# sine_wave_generator.net
KiCad netlist of a schematic drawn in Altium Designer
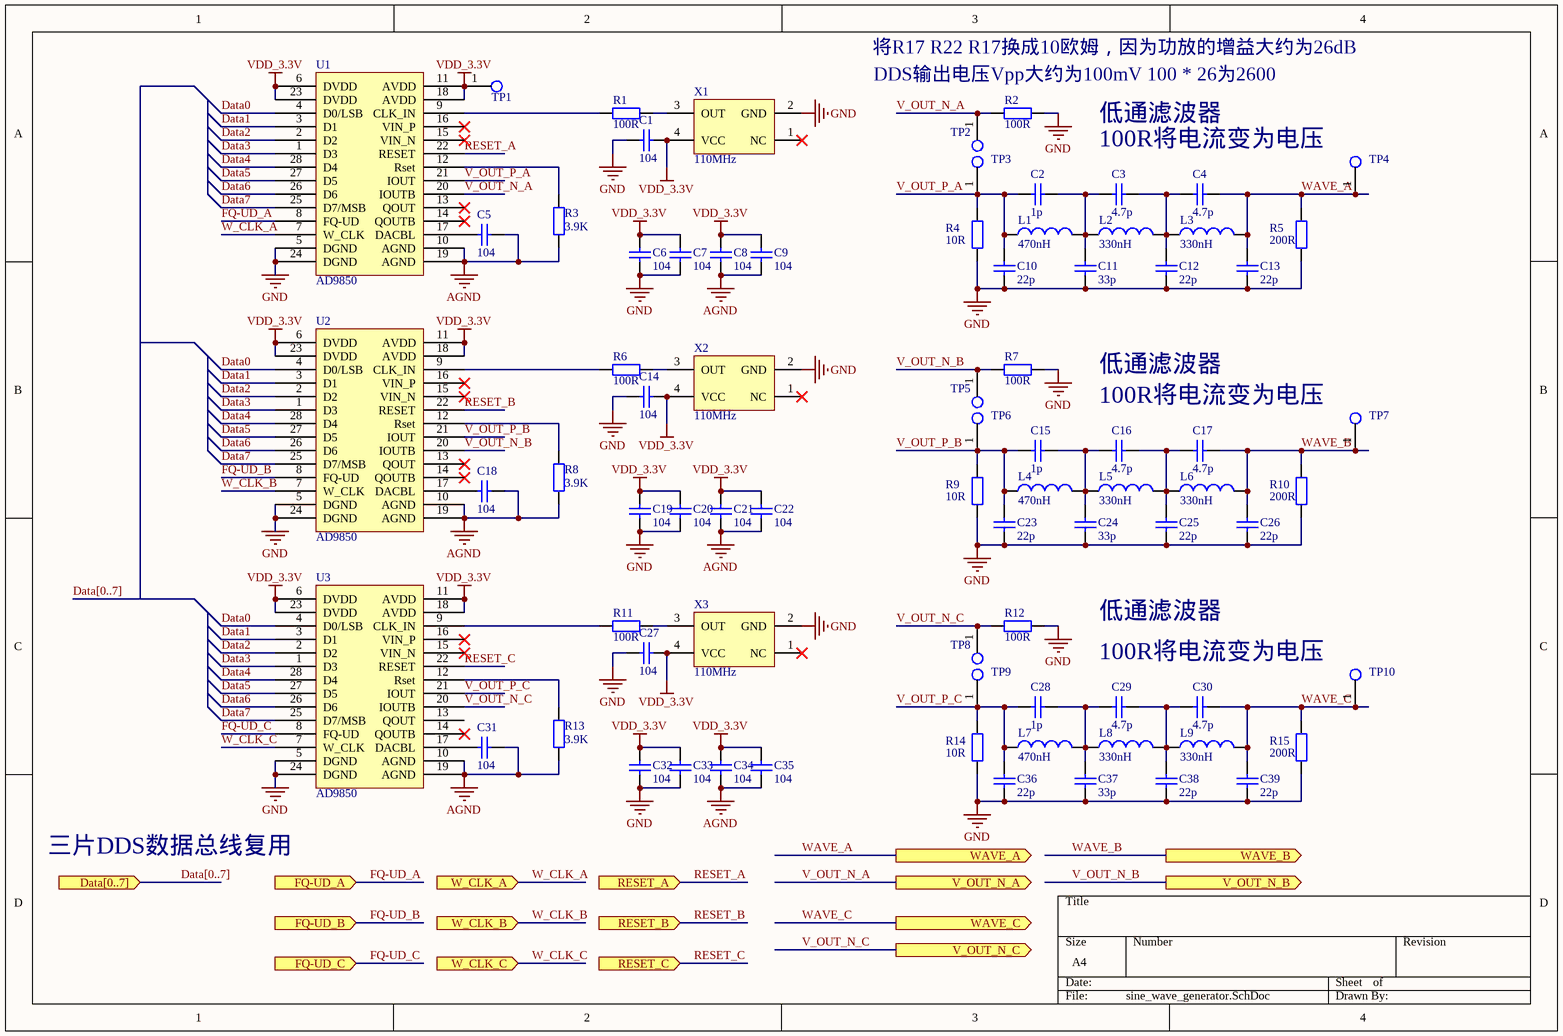
[diagram p0: sine_wave_generator.SchDoc]

(export (version "E")
  (design (tool "Eeschema 10.0.6"))
  (components
    (comp (ref "C1")
      (value "104")
      (footprint "0805")
      (fields (field (name "Comment") "Cap"))
      (libsource (lib "自动化研究所集成库20170318") (part "Cap"))
    )
    (comp (ref "C2")
      (value "1p")
      (footprint "0805")
      (fields (field (name "Comment") "Cap"))
      (libsource (lib "自动化研究所集成库20170318") (part "Cap"))
    )
    (comp (ref "C3")
      (value "4.7p")
      (footprint "0805")
      (fields (field (name "Comment") "Cap"))
      (libsource (lib "自动化研究所集成库20170318") (part "Cap"))
    )
    (comp (ref "C4")
      (value "4.7p")
      (footprint "0805")
      (fields (field (name "Comment") "Cap"))
      (libsource (lib "自动化研究所集成库20170318") (part "Cap"))
    )
    (comp (ref "C5")
      (value "104")
      (footprint "0805")
      (fields (field (name "Comment") "Cap"))
      (libsource (lib "自动化研究所集成库20170318") (part "Cap"))
    )
    (comp (ref "C6")
      (value "104")
      (footprint "0805")
      (fields (field (name "Comment") "Cap"))
      (libsource (lib "自动化研究所集成库20170318") (part "Cap"))
    )
    (comp (ref "C7")
      (value "104")
      (footprint "0805")
      (fields (field (name "Comment") "Cap"))
      (libsource (lib "自动化研究所集成库20170318") (part "Cap"))
    )
    (comp (ref "C8")
      (value "104")
      (footprint "0805")
      (fields (field (name "Comment") "Cap"))
      (libsource (lib "自动化研究所集成库20170318") (part "Cap"))
    )
    (comp (ref "C9")
      (value "104")
      (footprint "0805")
      (fields (field (name "Comment") "Cap"))
      (libsource (lib "自动化研究所集成库20170318") (part "Cap"))
    )
    (comp (ref "C10")
      (value "22p")
      (footprint "0805")
      (fields (field (name "Comment") "Cap"))
      (libsource (lib "自动化研究所集成库20170318") (part "Cap"))
    )
    (comp (ref "C11")
      (value "33p")
      (footprint "0805")
      (fields (field (name "Comment") "Cap"))
      (libsource (lib "自动化研究所集成库20170318") (part "Cap"))
    )
    (comp (ref "C12")
      (value "22p")
      (footprint "0805")
      (fields (field (name "Comment") "Cap"))
      (libsource (lib "自动化研究所集成库20170318") (part "Cap"))
    )
    (comp (ref "C13")
      (value "22p")
      (footprint "0805")
      (fields (field (name "Comment") "Cap"))
      (libsource (lib "自动化研究所集成库20170318") (part "Cap"))
    )
    (comp (ref "C14")
      (value "104")
      (footprint "0805")
      (fields (field (name "Comment") "Cap"))
      (libsource (lib "自动化研究所集成库20170318") (part "Cap"))
    )
    (comp (ref "C15")
      (value "1p")
      (footprint "0805")
      (fields (field (name "Comment") "Cap"))
      (libsource (lib "自动化研究所集成库20170318") (part "Cap"))
    )
    (comp (ref "C16")
      (value "4.7p")
      (footprint "0805")
      (fields (field (name "Comment") "Cap"))
      (libsource (lib "自动化研究所集成库20170318") (part "Cap"))
    )
    (comp (ref "C17")
      (value "4.7p")
      (footprint "0805")
      (fields (field (name "Comment") "Cap"))
      (libsource (lib "自动化研究所集成库20170318") (part "Cap"))
    )
    (comp (ref "C18")
      (value "104")
      (footprint "0805")
      (fields (field (name "Comment") "Cap"))
      (libsource (lib "自动化研究所集成库20170318") (part "Cap"))
    )
    (comp (ref "C19")
      (value "104")
      (footprint "0805")
      (fields (field (name "Comment") "Cap"))
      (libsource (lib "自动化研究所集成库20170318") (part "Cap"))
    )
    (comp (ref "C20")
      (value "104")
      (footprint "0805")
      (fields (field (name "Comment") "Cap"))
      (libsource (lib "自动化研究所集成库20170318") (part "Cap"))
    )
    (comp (ref "C21")
      (value "104")
      (footprint "0805")
      (fields (field (name "Comment") "Cap"))
      (libsource (lib "自动化研究所集成库20170318") (part "Cap"))
    )
    (comp (ref "C22")
      (value "104")
      (footprint "0805")
      (fields (field (name "Comment") "Cap"))
      (libsource (lib "自动化研究所集成库20170318") (part "Cap"))
    )
    (comp (ref "C23")
      (value "22p")
      (footprint "0805")
      (fields (field (name "Comment") "Cap"))
      (libsource (lib "自动化研究所集成库20170318") (part "Cap"))
    )
    (comp (ref "C24")
      (value "33p")
      (footprint "0805")
      (fields (field (name "Comment") "Cap"))
      (libsource (lib "自动化研究所集成库20170318") (part "Cap"))
    )
    (comp (ref "C25")
      (value "22p")
      (footprint "0805")
      (fields (field (name "Comment") "Cap"))
      (libsource (lib "自动化研究所集成库20170318") (part "Cap"))
    )
    (comp (ref "C26")
      (value "22p")
      (footprint "0805")
      (fields (field (name "Comment") "Cap"))
      (libsource (lib "自动化研究所集成库20170318") (part "Cap"))
    )
    (comp (ref "C27")
      (value "104")
      (footprint "0805")
      (fields (field (name "Comment") "Cap"))
      (libsource (lib "自动化研究所集成库20170318") (part "Cap"))
    )
    (comp (ref "C28")
      (value "1p")
      (footprint "0805")
      (fields (field (name "Comment") "Cap"))
      (libsource (lib "自动化研究所集成库20170318") (part "Cap"))
    )
    (comp (ref "C29")
      (value "4.7p")
      (footprint "0805")
      (fields (field (name "Comment") "Cap"))
      (libsource (lib "自动化研究所集成库20170318") (part "Cap"))
    )
    (comp (ref "C30")
      (value "4.7p")
      (footprint "0805")
      (fields (field (name "Comment") "Cap"))
      (libsource (lib "自动化研究所集成库20170318") (part "Cap"))
    )
    (comp (ref "C31")
      (value "104")
      (footprint "0805")
      (fields (field (name "Comment") "Cap"))
      (libsource (lib "自动化研究所集成库20170318") (part "Cap"))
    )
    (comp (ref "C32")
      (value "104")
      (footprint "0805")
      (fields (field (name "Comment") "Cap"))
      (libsource (lib "自动化研究所集成库20170318") (part "Cap"))
    )
    (comp (ref "C33")
      (value "104")
      (footprint "0805")
      (fields (field (name "Comment") "Cap"))
      (libsource (lib "自动化研究所集成库20170318") (part "Cap"))
    )
    (comp (ref "C34")
      (value "104")
      (footprint "0805")
      (fields (field (name "Comment") "Cap"))
      (libsource (lib "自动化研究所集成库20170318") (part "Cap"))
    )
    (comp (ref "C35")
      (value "104")
      (footprint "0805")
      (fields (field (name "Comment") "Cap"))
      (libsource (lib "自动化研究所集成库20170318") (part "Cap"))
    )
    (comp (ref "C36")
      (value "22p")
      (footprint "0805")
      (fields (field (name "Comment") "Cap"))
      (libsource (lib "自动化研究所集成库20170318") (part "Cap"))
    )
    (comp (ref "C37")
      (value "33p")
      (footprint "0805")
      (fields (field (name "Comment") "Cap"))
      (libsource (lib "自动化研究所集成库20170318") (part "Cap"))
    )
    (comp (ref "C38")
      (value "22p")
      (footprint "0805")
      (fields (field (name "Comment") "Cap"))
      (libsource (lib "自动化研究所集成库20170318") (part "Cap"))
    )
    (comp (ref "C39")
      (value "22p")
      (footprint "0805")
      (fields (field (name "Comment") "Cap"))
      (libsource (lib "自动化研究所集成库20170318") (part "Cap"))
    )
    (comp (ref "L1") (value "470nH") (footprint "0805L") (libsource (lib "Spartan") (part "Inductor")))
    (comp (ref "L2") (value "330nH") (footprint "0805L") (libsource (lib "Spartan") (part "Inductor")))
    (comp (ref "L3") (value "330nH") (footprint "0805L") (libsource (lib "Spartan") (part "Inductor")))
    (comp (ref "L4") (value "470nH") (footprint "0805L") (libsource (lib "Spartan") (part "Inductor")))
    (comp (ref "L5") (value "330nH") (footprint "0805L") (libsource (lib "Spartan") (part "Inductor")))
    (comp (ref "L6") (value "330nH") (footprint "0805L") (libsource (lib "Spartan") (part "Inductor")))
    (comp (ref "L7") (value "470nH") (footprint "0805L") (libsource (lib "Spartan") (part "Inductor")))
    (comp (ref "L8") (value "330nH") (footprint "0805L") (libsource (lib "Spartan") (part "Inductor")))
    (comp (ref "L9") (value "330nH") (footprint "0805L") (libsource (lib "Spartan") (part "Inductor")))
    (comp (ref "R1")
      (value "100R")
      (footprint "0805")
      (fields (field (name "Comment") "Res"))
      (libsource (lib "") (part "Res_1"))
    )
    (comp (ref "R2")
      (value "100R")
      (footprint "0805")
      (fields (field (name "Comment") "Res"))
      (libsource (lib "") (part "Res_1"))
    )
    (comp (ref "R3")
      (value "3.9K")
      (footprint "0805")
      (fields (field (name "Comment") "Res"))
      (libsource (lib "自动化研究所集成库20170318") (part "Res"))
    )
    (comp (ref "R4")
      (value "10R")
      (footprint "0805")
      (fields (field (name "Comment") "Res"))
      (libsource (lib "自动化研究所集成库20170318") (part "Res"))
    )
    (comp (ref "R5")
      (value "200R")
      (footprint "0805")
      (fields (field (name "Comment") "Res"))
      (libsource (lib "自动化研究所集成库20170318") (part "Res"))
    )
    (comp (ref "R6")
      (value "100R")
      (footprint "0805")
      (fields (field (name "Comment") "Res"))
      (libsource (lib "") (part "Res_1"))
    )
    (comp (ref "R7")
      (value "100R")
      (footprint "0805")
      (fields (field (name "Comment") "Res"))
      (libsource (lib "") (part "Res_1"))
    )
    (comp (ref "R8")
      (value "3.9K")
      (footprint "0805")
      (fields (field (name "Comment") "Res"))
      (libsource (lib "自动化研究所集成库20170318") (part "Res"))
    )
    (comp (ref "R9")
      (value "10R")
      (footprint "0805")
      (fields (field (name "Comment") "Res"))
      (libsource (lib "自动化研究所集成库20170318") (part "Res"))
    )
    (comp (ref "R10")
      (value "200R")
      (footprint "0805")
      (fields (field (name "Comment") "Res"))
      (libsource (lib "自动化研究所集成库20170318") (part "Res"))
    )
    (comp (ref "R11")
      (value "100R")
      (footprint "0805")
      (fields (field (name "Comment") "Res"))
      (libsource (lib "") (part "Res_1"))
    )
    (comp (ref "R12")
      (value "100R")
      (footprint "0805")
      (fields (field (name "Comment") "Res"))
      (libsource (lib "") (part "Res_1"))
    )
    (comp (ref "R13")
      (value "3.9K")
      (footprint "0805")
      (fields (field (name "Comment") "Res"))
      (libsource (lib "自动化研究所集成库20170318") (part "Res"))
    )
    (comp (ref "R14")
      (value "10R")
      (footprint "0805")
      (fields (field (name "Comment") "Res"))
      (libsource (lib "自动化研究所集成库20170318") (part "Res"))
    )
    (comp (ref "R15")
      (value "200R")
      (footprint "0805")
      (fields (field (name "Comment") "Res"))
      (libsource (lib "自动化研究所集成库20170318") (part "Res"))
    )
    (comp (ref "TP1") (value "testPoint") (footprint "TP_H") (libsource (lib "Spartan") (part "TP")))
    (comp (ref "TP2") (value "testPoint") (footprint "TP_H") (libsource (lib "Spartan") (part "TP")))
    (comp (ref "TP3") (value "testPoint") (footprint "TP_H") (libsource (lib "Spartan") (part "TP")))
    (comp (ref "TP4") (value "testPoint") (footprint "TP_H") (libsource (lib "Spartan") (part "TP")))
    (comp (ref "TP5") (value "testPoint") (footprint "TP_H") (libsource (lib "Spartan") (part "TP")))
    (comp (ref "TP6") (value "testPoint") (footprint "TP_H") (libsource (lib "Spartan") (part "TP")))
    (comp (ref "TP7") (value "testPoint") (footprint "TP_H") (libsource (lib "Spartan") (part "TP")))
    (comp (ref "TP8") (value "testPoint") (footprint "TP_H") (libsource (lib "Spartan") (part "TP")))
    (comp (ref "TP9") (value "testPoint") (footprint "TP_H") (libsource (lib "Spartan") (part "TP")))
    (comp (ref "TP10") (value "testPoint") (footprint "TP_H") (libsource (lib "Spartan") (part "TP")))
    (comp (ref "U1")
      (value "AD9850")
      (footprint "SOP65P780X198-28N")
      (libsource (lib "Dugu") (part "AD9850"))
    )
    (comp (ref "U2")
      (value "AD9850")
      (footprint "SOP65P780X198-28N")
      (libsource (lib "Dugu") (part "AD9850"))
    )
    (comp (ref "U3")
      (value "AD9850")
      (footprint "SOP65P780X198-28N")
      (libsource (lib "Dugu") (part "AD9850"))
    )
    (comp (ref "X1")
      (value "110MHz")
      (footprint "3225")
      (libsource (lib "PulsePower-Buck") (part "Oscillator"))
    )
    (comp (ref "X2")
      (value "110MHz")
      (footprint "3225")
      (libsource (lib "PulsePower-Buck") (part "Oscillator"))
    )
    (comp (ref "X3")
      (value "110MHz")
      (footprint "3225")
      (libsource (lib "PulsePower-Buck") (part "Oscillator"))
    )
  )
  (nets
    (net (code "1") (name "/Data0") (class "Default")
      (node (ref "U1") (pin "4") (pinfunction "D0/LSB_4") (pintype "passive"))
      (node (ref "U2") (pin "4") (pinfunction "D0/LSB_4") (pintype "passive"))
      (node (ref "U3") (pin "4") (pinfunction "D0/LSB_4") (pintype "passive"))
    )
    (net (code "2") (name "/Data1") (class "Default")
      (node (ref "U1") (pin "3") (pinfunction "D1_3") (pintype "passive"))
      (node (ref "U2") (pin "3") (pinfunction "D1_3") (pintype "passive"))
      (node (ref "U3") (pin "3") (pinfunction "D1_3") (pintype "passive"))
    )
    (net (code "3") (name "/Data2") (class "Default")
      (node (ref "U1") (pin "2") (pinfunction "D2_2") (pintype "passive"))
      (node (ref "U2") (pin "2") (pinfunction "D2_2") (pintype "passive"))
      (node (ref "U3") (pin "2") (pinfunction "D2_2") (pintype "passive"))
    )
    (net (code "4") (name "/Data3") (class "Default")
      (node (ref "U1") (pin "1") (pinfunction "D3_1") (pintype "passive"))
      (node (ref "U2") (pin "1") (pinfunction "D3_1") (pintype "passive"))
      (node (ref "U3") (pin "1") (pinfunction "D3_1") (pintype "passive"))
    )
    (net (code "5") (name "/Data4") (class "Default")
      (node (ref "U1") (pin "28") (pinfunction "D4_28") (pintype "passive"))
      (node (ref "U2") (pin "28") (pinfunction "D4_28") (pintype "passive"))
      (node (ref "U3") (pin "28") (pinfunction "D4_28") (pintype "passive"))
    )
    (net (code "6") (name "/Data5") (class "Default")
      (node (ref "U1") (pin "27") (pinfunction "D5_27") (pintype "passive"))
      (node (ref "U2") (pin "27") (pinfunction "D5_27") (pintype "passive"))
      (node (ref "U3") (pin "27") (pinfunction "D5_27") (pintype "passive"))
    )
    (net (code "7") (name "/Data6") (class "Default")
      (node (ref "U1") (pin "26") (pinfunction "D6_26") (pintype "passive"))
      (node (ref "U2") (pin "26") (pinfunction "D6_26") (pintype "passive"))
      (node (ref "U3") (pin "26") (pinfunction "D6_26") (pintype "passive"))
    )
    (net (code "8") (name "/Data7") (class "Default")
      (node (ref "U1") (pin "25") (pinfunction "D7/MSB_25") (pintype "passive"))
      (node (ref "U2") (pin "25") (pinfunction "D7/MSB_25") (pintype "passive"))
      (node (ref "U3") (pin "25") (pinfunction "D7/MSB_25") (pintype "passive"))
    )
    (net (code "10") (name "/FQ-UD_A") (class "Default")
      (node (ref "U1") (pin "8") (pinfunction "FQ-UD_8") (pintype "passive"))
    )
    (net (code "11") (name "/FQ-UD_B") (class "Default")
      (node (ref "U2") (pin "8") (pinfunction "FQ-UD_8") (pintype "passive"))
    )
    (net (code "12") (name "/FQ-UD_C") (class "Default")
      (node (ref "U3") (pin "8") (pinfunction "FQ-UD_8") (pintype "passive"))
    )
    (net (code "13") (name "/RESET_A") (class "Default")
      (node (ref "U1") (pin "22") (pinfunction "RESET_22") (pintype "passive"))
    )
    (net (code "14") (name "/RESET_B") (class "Default")
      (node (ref "U2") (pin "22") (pinfunction "RESET_22") (pintype "passive"))
    )
    (net (code "15") (name "/RESET_C") (class "Default")
      (node (ref "U3") (pin "22") (pinfunction "RESET_22") (pintype "passive"))
    )
    (net (code "16") (name "/V_OUT_N_A") (class "Default")
      (node (ref "R2") (pin "1") (pinfunction "1_1") (pintype "passive"))
      (node (ref "TP2") (pin "1") (pinfunction "1_1") (pintype "passive"))
      (node (ref "U1") (pin "20") (pinfunction "IOUTB_20") (pintype "passive"))
    )
    (net (code "17") (name "/V_OUT_N_B") (class "Default")
      (node (ref "R7") (pin "1") (pinfunction "1_1") (pintype "passive"))
      (node (ref "TP5") (pin "1") (pinfunction "1_1") (pintype "passive"))
      (node (ref "U2") (pin "20") (pinfunction "IOUTB_20") (pintype "passive"))
    )
    (net (code "18") (name "/V_OUT_N_C") (class "Default")
      (node (ref "R12") (pin "1") (pinfunction "1_1") (pintype "passive"))
      (node (ref "TP8") (pin "1") (pinfunction "1_1") (pintype "passive"))
      (node (ref "U3") (pin "20") (pinfunction "IOUTB_20") (pintype "passive"))
    )
    (net (code "19") (name "/V_OUT_P_A") (class "Default")
      (node (ref "C10") (pin "2") (pinfunction "2_2") (pintype "passive"))
      (node (ref "C2") (pin "1") (pinfunction "1_1") (pintype "passive"))
      (node (ref "L1") (pin "1") (pinfunction "1_1") (pintype "passive"))
      (node (ref "R4") (pin "2") (pinfunction "2_2") (pintype "passive"))
      (node (ref "TP3") (pin "1") (pinfunction "1_1") (pintype "passive"))
      (node (ref "U1") (pin "21") (pinfunction "IOUT_21") (pintype "passive"))
    )
    (net (code "20") (name "/V_OUT_P_B") (class "Default")
      (node (ref "C15") (pin "1") (pinfunction "1_1") (pintype "passive"))
      (node (ref "C23") (pin "2") (pinfunction "2_2") (pintype "passive"))
      (node (ref "L4") (pin "1") (pinfunction "1_1") (pintype "passive"))
      (node (ref "R9") (pin "2") (pinfunction "2_2") (pintype "passive"))
      (node (ref "TP6") (pin "1") (pinfunction "1_1") (pintype "passive"))
      (node (ref "U2") (pin "21") (pinfunction "IOUT_21") (pintype "passive"))
    )
    (net (code "21") (name "/V_OUT_P_C") (class "Default")
      (node (ref "C28") (pin "1") (pinfunction "1_1") (pintype "passive"))
      (node (ref "C36") (pin "2") (pinfunction "2_2") (pintype "passive"))
      (node (ref "L7") (pin "1") (pinfunction "1_1") (pintype "passive"))
      (node (ref "R14") (pin "2") (pinfunction "2_2") (pintype "passive"))
      (node (ref "TP9") (pin "1") (pinfunction "1_1") (pintype "passive"))
      (node (ref "U3") (pin "21") (pinfunction "IOUT_21") (pintype "passive"))
    )
    (net (code "22") (name "/WAVE_A") (class "Default")
      (node (ref "C13") (pin "2") (pinfunction "2_2") (pintype "passive"))
      (node (ref "C4") (pin "2") (pinfunction "2_2") (pintype "passive"))
      (node (ref "L3") (pin "2") (pinfunction "2_2") (pintype "passive"))
      (node (ref "R5") (pin "2") (pinfunction "2_2") (pintype "passive"))
      (node (ref "TP4") (pin "1") (pinfunction "1_1") (pintype "passive"))
    )
    (net (code "23") (name "/WAVE_B") (class "Default")
      (node (ref "C17") (pin "2") (pinfunction "2_2") (pintype "passive"))
      (node (ref "C26") (pin "2") (pinfunction "2_2") (pintype "passive"))
      (node (ref "L6") (pin "2") (pinfunction "2_2") (pintype "passive"))
      (node (ref "R10") (pin "2") (pinfunction "2_2") (pintype "passive"))
      (node (ref "TP7") (pin "1") (pinfunction "1_1") (pintype "passive"))
    )
    (net (code "24") (name "/WAVE_C") (class "Default")
      (node (ref "C30") (pin "2") (pinfunction "2_2") (pintype "passive"))
      (node (ref "C39") (pin "2") (pinfunction "2_2") (pintype "passive"))
      (node (ref "L9") (pin "2") (pinfunction "2_2") (pintype "passive"))
      (node (ref "R15") (pin "2") (pinfunction "2_2") (pintype "passive"))
      (node (ref "TP10") (pin "1") (pinfunction "1_1") (pintype "passive"))
    )
    (net (code "25") (name "/W_CLK_A") (class "Default")
      (node (ref "U1") (pin "7") (pinfunction "W_CLK_7") (pintype "passive"))
    )
    (net (code "26") (name "/W_CLK_B") (class "Default")
      (node (ref "U2") (pin "7") (pinfunction "W_CLK_7") (pintype "passive"))
    )
    (net (code "27") (name "/W_CLK_C") (class "Default")
      (node (ref "U3") (pin "7") (pinfunction "W_CLK_7") (pintype "passive"))
    )
    (net (code "28") (name "AGND") (class "Default")
      (node (ref "C18") (pin "2") (pinfunction "2_2") (pintype "passive"))
      (node (ref "C21") (pin "1") (pinfunction "1_1") (pintype "passive"))
      (node (ref "C22") (pin "1") (pinfunction "1_1") (pintype "passive"))
      (node (ref "C31") (pin "1") (pinfunction "1_1") (pintype "passive"))
      (node (ref "C34") (pin "1") (pinfunction "1_1") (pintype "passive"))
      (node (ref "C35") (pin "1") (pinfunction "1_1") (pintype "passive"))
      (node (ref "C5") (pin "2") (pinfunction "2_2") (pintype "passive"))
      (node (ref "C8") (pin "1") (pinfunction "1_1") (pintype "passive"))
      (node (ref "C9") (pin "1") (pinfunction "1_1") (pintype "passive"))
      (node (ref "R13") (pin "1") (pinfunction "1_1") (pintype "passive"))
      (node (ref "R3") (pin "1") (pinfunction "1_1") (pintype "passive"))
      (node (ref "R8") (pin "1") (pinfunction "1_1") (pintype "passive"))
      (node (ref "U1") (pin "10") (pinfunction "AGND_10") (pintype "power_in"))
      (node (ref "U1") (pin "19") (pinfunction "AGND_19") (pintype "passive"))
      (node (ref "U2") (pin "10") (pinfunction "AGND_10") (pintype "power_in"))
      (node (ref "U2") (pin "19") (pinfunction "AGND_19") (pintype "passive"))
      (node (ref "U3") (pin "10") (pinfunction "AGND_10") (pintype "power_in"))
      (node (ref "U3") (pin "19") (pinfunction "AGND_19") (pintype "passive"))
    )
    (net (code "29") (name "GND") (class "Default")
      (node (ref "C1") (pin "1") (pinfunction "1_1") (pintype "passive"))
      (node (ref "C10") (pin "1") (pinfunction "1_1") (pintype "passive"))
      (node (ref "C11") (pin "1") (pinfunction "1_1") (pintype "passive"))
      (node (ref "C12") (pin "1") (pinfunction "1_1") (pintype "passive"))
      (node (ref "C13") (pin "1") (pinfunction "1_1") (pintype "passive"))
      (node (ref "C14") (pin "1") (pinfunction "1_1") (pintype "passive"))
      (node (ref "C19") (pin "1") (pinfunction "1_1") (pintype "passive"))
      (node (ref "C20") (pin "1") (pinfunction "1_1") (pintype "passive"))
      (node (ref "C23") (pin "1") (pinfunction "1_1") (pintype "passive"))
      (node (ref "C24") (pin "1") (pinfunction "1_1") (pintype "passive"))
      (node (ref "C25") (pin "1") (pinfunction "1_1") (pintype "passive"))
      (node (ref "C26") (pin "1") (pinfunction "1_1") (pintype "passive"))
      (node (ref "C27") (pin "2") (pinfunction "2_2") (pintype "passive"))
      (node (ref "C32") (pin "1") (pinfunction "1_1") (pintype "passive"))
      (node (ref "C33") (pin "1") (pinfunction "1_1") (pintype "passive"))
      (node (ref "C36") (pin "1") (pinfunction "1_1") (pintype "passive"))
      (node (ref "C37") (pin "1") (pinfunction "1_1") (pintype "passive"))
      (node (ref "C38") (pin "1") (pinfunction "1_1") (pintype "passive"))
      (node (ref "C39") (pin "1") (pinfunction "1_1") (pintype "passive"))
      (node (ref "C6") (pin "1") (pinfunction "1_1") (pintype "passive"))
      (node (ref "C7") (pin "1") (pinfunction "1_1") (pintype "passive"))
      (node (ref "R10") (pin "1") (pinfunction "1_1") (pintype "passive"))
      (node (ref "R12") (pin "2") (pinfunction "2_2") (pintype "passive"))
      (node (ref "R14") (pin "1") (pinfunction "1_1") (pintype "passive"))
      (node (ref "R15") (pin "1") (pinfunction "1_1") (pintype "passive"))
      (node (ref "R2") (pin "2") (pinfunction "2_2") (pintype "passive"))
      (node (ref "R4") (pin "1") (pinfunction "1_1") (pintype "passive"))
      (node (ref "R5") (pin "1") (pinfunction "1_1") (pintype "passive"))
      (node (ref "R7") (pin "2") (pinfunction "2_2") (pintype "passive"))
      (node (ref "R9") (pin "1") (pinfunction "1_1") (pintype "passive"))
      (node (ref "U1") (pin "24") (pinfunction "DGND_24") (pintype "passive"))
      (node (ref "U1") (pin "5") (pinfunction "DGND_5") (pintype "passive"))
      (node (ref "U2") (pin "24") (pinfunction "DGND_24") (pintype "passive"))
      (node (ref "U2") (pin "5") (pinfunction "DGND_5") (pintype "passive"))
      (node (ref "U3") (pin "24") (pinfunction "DGND_24") (pintype "passive"))
      (node (ref "U3") (pin "5") (pinfunction "DGND_5") (pintype "passive"))
      (node (ref "X1") (pin "2") (pinfunction "GND_2") (pintype "passive"))
      (node (ref "X2") (pin "2") (pinfunction "GND_2") (pintype "passive"))
      (node (ref "X3") (pin "2") (pinfunction "GND_2") (pintype "passive"))
    )
    (net (code "30") (name "Net-(C11-Pad2)") (class "Default")
      (node (ref "C11") (pin "2") (pinfunction "2_2") (pintype "passive"))
      (node (ref "C2") (pin "2") (pinfunction "2_2") (pintype "passive"))
      (node (ref "C3") (pin "1") (pinfunction "1_1") (pintype "passive"))
      (node (ref "L1") (pin "2") (pinfunction "2_2") (pintype "passive"))
      (node (ref "L2") (pin "1") (pinfunction "1_1") (pintype "passive"))
    )
    (net (code "31") (name "Net-(C12-Pad2)") (class "Default")
      (node (ref "C12") (pin "2") (pinfunction "2_2") (pintype "passive"))
      (node (ref "C3") (pin "2") (pinfunction "2_2") (pintype "passive"))
      (node (ref "C4") (pin "1") (pinfunction "1_1") (pintype "passive"))
      (node (ref "L2") (pin "2") (pinfunction "2_2") (pintype "passive"))
      (node (ref "L3") (pin "1") (pinfunction "1_1") (pintype "passive"))
    )
    (net (code "32") (name "Net-(C15-Pad2)") (class "Default")
      (node (ref "C15") (pin "2") (pinfunction "2_2") (pintype "passive"))
      (node (ref "C16") (pin "1") (pinfunction "1_1") (pintype "passive"))
      (node (ref "C24") (pin "2") (pinfunction "2_2") (pintype "passive"))
      (node (ref "L4") (pin "2") (pinfunction "2_2") (pintype "passive"))
      (node (ref "L5") (pin "1") (pinfunction "1_1") (pintype "passive"))
    )
    (net (code "33") (name "Net-(C16-Pad2)") (class "Default")
      (node (ref "C16") (pin "2") (pinfunction "2_2") (pintype "passive"))
      (node (ref "C17") (pin "1") (pinfunction "1_1") (pintype "passive"))
      (node (ref "C25") (pin "2") (pinfunction "2_2") (pintype "passive"))
      (node (ref "L5") (pin "2") (pinfunction "2_2") (pintype "passive"))
      (node (ref "L6") (pin "1") (pinfunction "1_1") (pintype "passive"))
    )
    (net (code "34") (name "Net-(C28-Pad2)") (class "Default")
      (node (ref "C28") (pin "2") (pinfunction "2_2") (pintype "passive"))
      (node (ref "C29") (pin "1") (pinfunction "1_1") (pintype "passive"))
      (node (ref "C37") (pin "2") (pinfunction "2_2") (pintype "passive"))
      (node (ref "L7") (pin "2") (pinfunction "2_2") (pintype "passive"))
      (node (ref "L8") (pin "1") (pinfunction "1_1") (pintype "passive"))
    )
    (net (code "35") (name "Net-(C29-Pad2)") (class "Default")
      (node (ref "C29") (pin "2") (pinfunction "2_2") (pintype "passive"))
      (node (ref "C30") (pin "1") (pinfunction "1_1") (pintype "passive"))
      (node (ref "C38") (pin "2") (pinfunction "2_2") (pintype "passive"))
      (node (ref "L8") (pin "2") (pinfunction "2_2") (pintype "passive"))
      (node (ref "L9") (pin "1") (pinfunction "1_1") (pintype "passive"))
    )
    (net (code "36") (name "Net-(U1-CLK_IN)") (class "Default")
      (node (ref "R1") (pin "1") (pinfunction "1_1") (pintype "passive"))
      (node (ref "U1") (pin "9") (pinfunction "CLK_IN_9") (pintype "passive"))
    )
    (net (code "37") (name "Net-(U1-DACBL)") (class "Default")
      (node (ref "C5") (pin "1") (pinfunction "1_1") (pintype "passive"))
      (node (ref "U1") (pin "17") (pinfunction "DACBL_17") (pintype "passive"))
    )
    (net (code "38") (name "Net-(U1-Rset)") (class "Default")
      (node (ref "R3") (pin "2") (pinfunction "2_2") (pintype "passive"))
      (node (ref "U1") (pin "12") (pinfunction "Rset_12") (pintype "passive"))
    )
    (net (code "39") (name "Net-(U2-CLK_IN)") (class "Default")
      (node (ref "R6") (pin "1") (pinfunction "1_1") (pintype "passive"))
      (node (ref "U2") (pin "9") (pinfunction "CLK_IN_9") (pintype "passive"))
    )
    (net (code "40") (name "Net-(U2-DACBL)") (class "Default")
      (node (ref "C18") (pin "1") (pinfunction "1_1") (pintype "passive"))
      (node (ref "U2") (pin "17") (pinfunction "DACBL_17") (pintype "passive"))
    )
    (net (code "41") (name "Net-(U2-Rset)") (class "Default")
      (node (ref "R8") (pin "2") (pinfunction "2_2") (pintype "passive"))
      (node (ref "U2") (pin "12") (pinfunction "Rset_12") (pintype "passive"))
    )
    (net (code "42") (name "Net-(U3-CLK_IN)") (class "Default")
      (node (ref "R11") (pin "1") (pinfunction "1_1") (pintype "passive"))
      (node (ref "U3") (pin "9") (pinfunction "CLK_IN_9") (pintype "passive"))
    )
    (net (code "43") (name "Net-(U3-DACBL)") (class "Default")
      (node (ref "C31") (pin "2") (pinfunction "2_2") (pintype "passive"))
      (node (ref "U3") (pin "17") (pinfunction "DACBL_17") (pintype "passive"))
    )
    (net (code "44") (name "Net-(U3-Rset)") (class "Default")
      (node (ref "R13") (pin "2") (pinfunction "2_2") (pintype "passive"))
      (node (ref "U3") (pin "12") (pinfunction "Rset_12") (pintype "passive"))
    )
    (net (code "45") (name "Net-(X1-OUT)") (class "Default")
      (node (ref "R1") (pin "2") (pinfunction "2_2") (pintype "passive"))
      (node (ref "X1") (pin "3") (pinfunction "OUT_3") (pintype "passive"))
    )
    (net (code "46") (name "Net-(X2-OUT)") (class "Default")
      (node (ref "R6") (pin "2") (pinfunction "2_2") (pintype "passive"))
      (node (ref "X2") (pin "3") (pinfunction "OUT_3") (pintype "passive"))
    )
    (net (code "47") (name "Net-(X3-OUT)") (class "Default")
      (node (ref "R11") (pin "2") (pinfunction "2_2") (pintype "passive"))
      (node (ref "X3") (pin "3") (pinfunction "OUT_3") (pintype "passive"))
    )
    (net (code "48") (name "VDD_3.3V") (class "Default")
      (node (ref "C1") (pin "2") (pinfunction "2_2") (pintype "passive"))
      (node (ref "C14") (pin "2") (pinfunction "2_2") (pintype "passive"))
      (node (ref "C19") (pin "2") (pinfunction "2_2") (pintype "passive"))
      (node (ref "C20") (pin "2") (pinfunction "2_2") (pintype "passive"))
      (node (ref "C21") (pin "2") (pinfunction "2_2") (pintype "passive"))
      (node (ref "C22") (pin "2") (pinfunction "2_2") (pintype "passive"))
      (node (ref "C27") (pin "1") (pinfunction "1_1") (pintype "passive"))
      (node (ref "C32") (pin "2") (pinfunction "2_2") (pintype "passive"))
      (node (ref "C33") (pin "2") (pinfunction "2_2") (pintype "passive"))
      (node (ref "C34") (pin "2") (pinfunction "2_2") (pintype "passive"))
      (node (ref "C35") (pin "2") (pinfunction "2_2") (pintype "passive"))
      (node (ref "C6") (pin "2") (pinfunction "2_2") (pintype "passive"))
      (node (ref "C7") (pin "2") (pinfunction "2_2") (pintype "passive"))
      (node (ref "C8") (pin "2") (pinfunction "2_2") (pintype "passive"))
      (node (ref "C9") (pin "2") (pinfunction "2_2") (pintype "passive"))
      (node (ref "TP1") (pin "1") (pinfunction "1_1") (pintype "passive"))
      (node (ref "U1") (pin "11") (pinfunction "AVDD_11") (pintype "passive"))
      (node (ref "U1") (pin "18") (pinfunction "AVDD_18") (pintype "passive"))
      (node (ref "U1") (pin "23") (pinfunction "DVDD_23") (pintype "passive"))
      (node (ref "U1") (pin "6") (pinfunction "DVDD_6") (pintype "passive"))
      (node (ref "U2") (pin "11") (pinfunction "AVDD_11") (pintype "passive"))
      (node (ref "U2") (pin "18") (pinfunction "AVDD_18") (pintype "passive"))
      (node (ref "U2") (pin "23") (pinfunction "DVDD_23") (pintype "passive"))
      (node (ref "U2") (pin "6") (pinfunction "DVDD_6") (pintype "passive"))
      (node (ref "U3") (pin "11") (pinfunction "AVDD_11") (pintype "passive"))
      (node (ref "U3") (pin "18") (pinfunction "AVDD_18") (pintype "passive"))
      (node (ref "U3") (pin "23") (pinfunction "DVDD_23") (pintype "passive"))
      (node (ref "U3") (pin "6") (pinfunction "DVDD_6") (pintype "passive"))
      (node (ref "X1") (pin "4") (pinfunction "VCC_4") (pintype "passive"))
      (node (ref "X2") (pin "4") (pinfunction "VCC_4") (pintype "passive"))
      (node (ref "X3") (pin "4") (pinfunction "VCC_4") (pintype "passive"))
    )
    (net (code "49") (name "unconnected-(U1-QOUT-Pad13)") (class "Default")
      (node (ref "U1") (pin "13") (pinfunction "QOUT_13") (pintype "passive+no_connect"))
    )
    (net (code "50") (name "unconnected-(U1-QOUTB-Pad14)") (class "Default")
      (node (ref "U1") (pin "14") (pinfunction "QOUTB_14") (pintype "passive+no_connect"))
    )
    (net (code "51") (name "unconnected-(U1-VIN_N-Pad15)") (class "Default")
      (node (ref "U1") (pin "15") (pinfunction "VIN_N_15") (pintype "passive+no_connect"))
    )
    (net (code "52") (name "unconnected-(U1-VIN_P-Pad16)") (class "Default")
      (node (ref "U1") (pin "16") (pinfunction "VIN_P_16") (pintype "passive+no_connect"))
    )
    (net (code "53") (name "unconnected-(U2-QOUT-Pad13)") (class "Default")
      (node (ref "U2") (pin "13") (pinfunction "QOUT_13") (pintype "passive+no_connect"))
    )
    (net (code "54") (name "unconnected-(U2-QOUTB-Pad14)") (class "Default")
      (node (ref "U2") (pin "14") (pinfunction "QOUTB_14") (pintype "passive+no_connect"))
    )
    (net (code "55") (name "unconnected-(U2-VIN_N-Pad15)") (class "Default")
      (node (ref "U2") (pin "15") (pinfunction "VIN_N_15") (pintype "passive+no_connect"))
    )
    (net (code "56") (name "unconnected-(U2-VIN_P-Pad16)") (class "Default")
      (node (ref "U2") (pin "16") (pinfunction "VIN_P_16") (pintype "passive+no_connect"))
    )
    (net (code "57") (name "unconnected-(U3-QOUT-Pad13)") (class "Default")
      (node (ref "U3") (pin "13") (pinfunction "QOUT_13") (pintype "passive"))
    )
    (net (code "58") (name "unconnected-(U3-QOUTB-Pad14)") (class "Default")
      (node (ref "U3") (pin "14") (pinfunction "QOUTB_14") (pintype "passive+no_connect"))
    )
    (net (code "59") (name "unconnected-(U3-VIN_N-Pad15)") (class "Default")
      (node (ref "U3") (pin "15") (pinfunction "VIN_N_15") (pintype "passive+no_connect"))
    )
    (net (code "60") (name "unconnected-(U3-VIN_P-Pad16)") (class "Default")
      (node (ref "U3") (pin "16") (pinfunction "VIN_P_16") (pintype "passive+no_connect"))
    )
    (net (code "61") (name "unconnected-(X1-NC-Pad1)") (class "Default")
      (node (ref "X1") (pin "1") (pinfunction "NC_1") (pintype "passive+no_connect"))
    )
    (net (code "62") (name "unconnected-(X2-NC-Pad1)") (class "Default")
      (node (ref "X2") (pin "1") (pinfunction "NC_1") (pintype "passive+no_connect"))
    )
    (net (code "63") (name "unconnected-(X3-NC-Pad1)") (class "Default")
      (node (ref "X3") (pin "1") (pinfunction "NC_1") (pintype "passive+no_connect"))
    )
  )
)
